# TouchController.net
KiCad netlist of a schematic drawn in Altium Designer
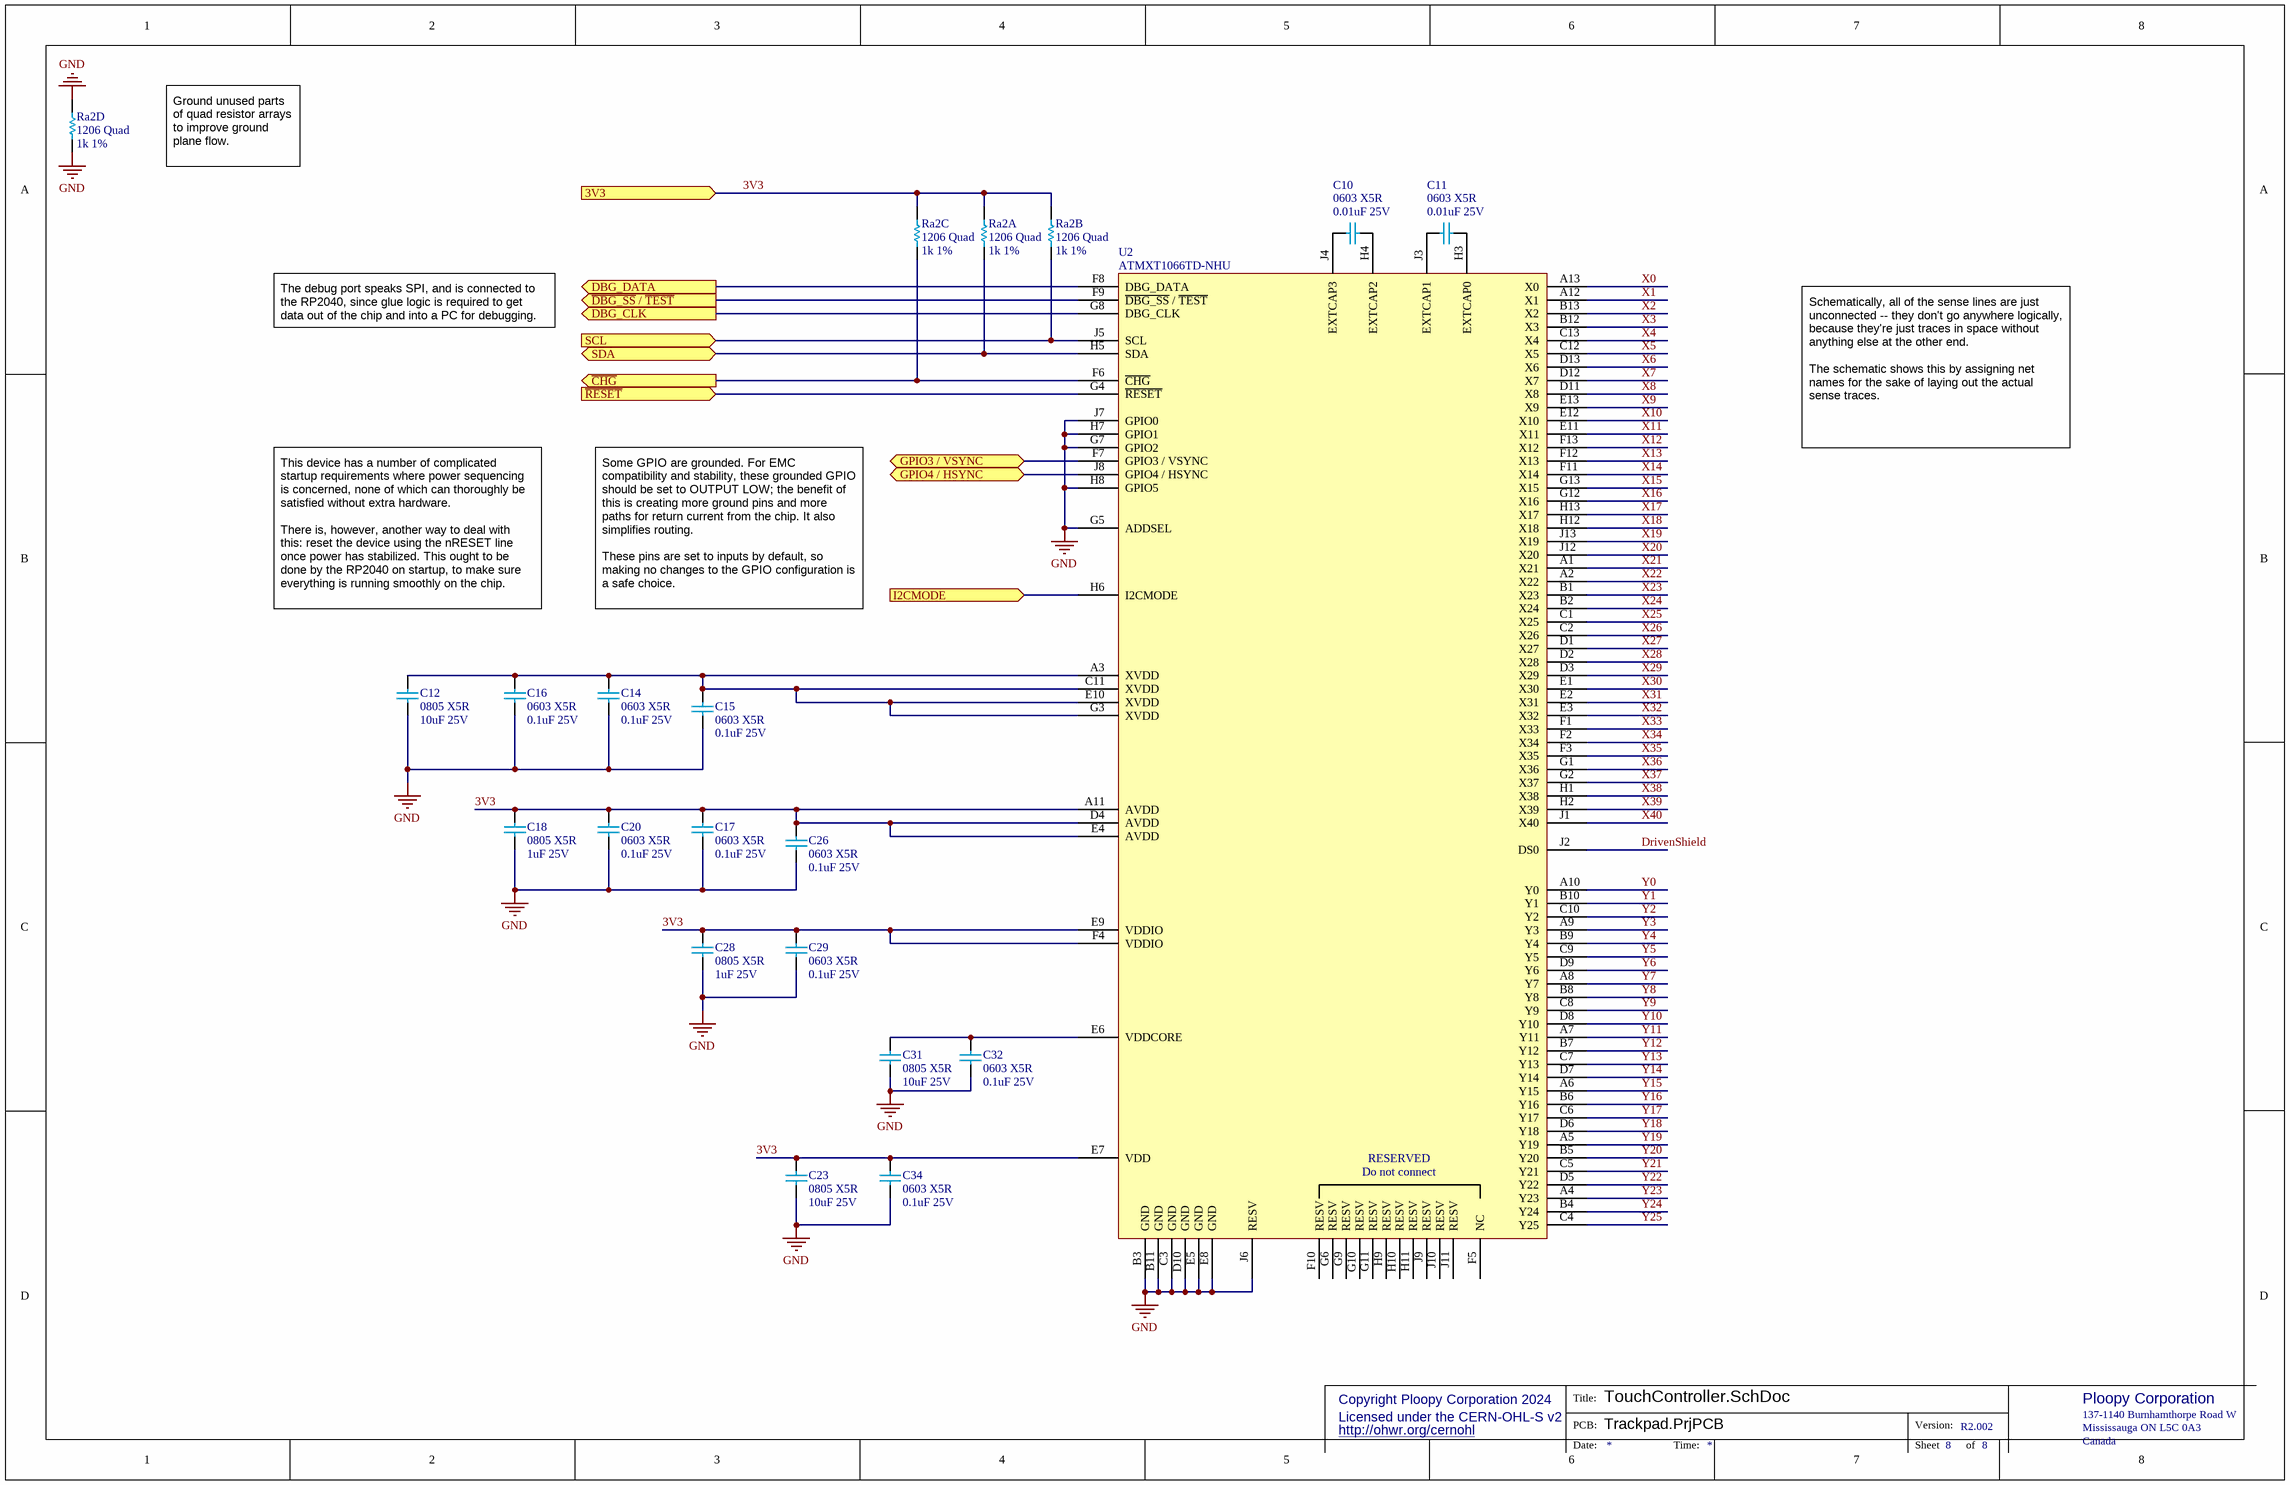
[diagram p0: TouchController.SchDoc]

(export (version "E")
  (design (tool "Eeschema 10.0.6"))
  (components
    (comp (ref "C10")
      (value "0603 X5R")
      (footprint "0603 capacitor - CAPC1608X06N")
      (description "0603, X5R or better")
      (fields (field (name "ALTIUM_VALUE") "0.01uF 25V"))
      (libsource (lib "Chip_Passives") (part "Cap 0.01uF 25V"))
    )
    (comp (ref "C11")
      (value "0603 X5R")
      (footprint "0603 capacitor - CAPC1608X06N")
      (description "0603, X5R or better")
      (fields (field (name "ALTIUM_VALUE") "0.01uF 25V"))
      (libsource (lib "Chip_Passives") (part "Cap 0.01uF 25V"))
    )
    (comp (ref "C12")
      (value "0805 X5R")
      (footprint "0805 - TALL")
      (description "0805, X5R or better")
      (fields (field (name "ALTIUM_VALUE") "10uF 25V"))
      (libsource (lib "Chip_Passives") (part "Cap 10uF 25V"))
    )
    (comp (ref "C14")
      (value "0603 X5R")
      (footprint "0603 capacitor - CAPC1608X06N")
      (description "0603, X5R or better")
      (fields (field (name "ALTIUM_VALUE") "0.1uF 25V"))
      (libsource (lib "Chip_Passives") (part "Cap 0.1uF 25V"))
    )
    (comp (ref "C15")
      (value "0603 X5R")
      (footprint "0603 capacitor - CAPC1608X06N")
      (description "0603, X5R or better")
      (fields (field (name "ALTIUM_VALUE") "0.1uF 25V"))
      (libsource (lib "Chip_Passives") (part "Cap 0.1uF 25V"))
    )
    (comp (ref "C16")
      (value "0603 X5R")
      (footprint "0603 capacitor - CAPC1608X06N")
      (description "0603, X5R or better")
      (fields (field (name "ALTIUM_VALUE") "0.1uF 25V"))
      (libsource (lib "Chip_Passives") (part "Cap 0.1uF 25V"))
    )
    (comp (ref "C17")
      (value "0603 X5R")
      (footprint "0603 capacitor - CAPC1608X06N")
      (description "0603, X5R or better")
      (fields (field (name "ALTIUM_VALUE") "0.1uF 25V"))
      (libsource (lib "Chip_Passives") (part "Cap 0.1uF 25V"))
    )
    (comp (ref "C18")
      (value "0805 X5R")
      (footprint "0805 - TALL")
      (description "0805, X5R or better")
      (fields (field (name "ALTIUM_VALUE") "1uF 25V"))
      (libsource (lib "Chip_Passives") (part "Cap 1uF 25V"))
    )
    (comp (ref "C20")
      (value "0603 X5R")
      (footprint "0603 capacitor - CAPC1608X06N")
      (description "0603, X5R or better")
      (fields (field (name "ALTIUM_VALUE") "0.1uF 25V"))
      (libsource (lib "Chip_Passives") (part "Cap 0.1uF 25V"))
    )
    (comp (ref "C23")
      (value "0805 X5R")
      (footprint "0805 - TALL")
      (description "0805, X5R or better")
      (fields (field (name "ALTIUM_VALUE") "10uF 25V"))
      (libsource (lib "Chip_Passives") (part "Cap 10uF 25V"))
    )
    (comp (ref "C26")
      (value "0603 X5R")
      (footprint "0603 capacitor - CAPC1608X06N")
      (description "0603, X5R or better")
      (fields (field (name "ALTIUM_VALUE") "0.1uF 25V"))
      (libsource (lib "Chip_Passives") (part "Cap 0.1uF 25V"))
    )
    (comp (ref "C28")
      (value "0805 X5R")
      (footprint "0805 - TALL")
      (description "0805, X5R or better")
      (fields (field (name "ALTIUM_VALUE") "1uF 25V"))
      (libsource (lib "Chip_Passives") (part "Cap 1uF 25V"))
    )
    (comp (ref "C29")
      (value "0603 X5R")
      (footprint "0603 capacitor - CAPC1608X06N")
      (description "0603, X5R or better")
      (fields (field (name "ALTIUM_VALUE") "0.1uF 25V"))
      (libsource (lib "Chip_Passives") (part "Cap 0.1uF 25V"))
    )
    (comp (ref "C31")
      (value "0805 X5R")
      (footprint "0805 - TALL")
      (description "0805, X5R or better")
      (fields (field (name "ALTIUM_VALUE") "10uF 25V"))
      (libsource (lib "Chip_Passives") (part "Cap 10uF 25V"))
    )
    (comp (ref "C32")
      (value "0603 X5R")
      (footprint "0603 capacitor - CAPC1608X06N")
      (description "0603, X5R or better")
      (fields (field (name "ALTIUM_VALUE") "0.1uF 25V"))
      (libsource (lib "Chip_Passives") (part "Cap 0.1uF 25V"))
    )
    (comp (ref "C34")
      (value "0603 X5R")
      (footprint "0603 capacitor - CAPC1608X06N")
      (description "0603, X5R or better")
      (fields (field (name "ALTIUM_VALUE") "0.1uF 25V"))
      (libsource (lib "Chip_Passives") (part "Cap 0.1uF 25V"))
    )
    (comp (ref "Ra2")
      (value "1206 Quad")
      (footprint "4x 1k 1% - CAC-80P320X160-8M")
      (description "Chip resistor")
      (fields (field (name "ALTIUM_VALUE") "1k 1%"))
      (libsource (lib "Chip_Passives") (part "Quad Res 1k 1% 1206"))
    )
    (comp (ref "U2")
      (value "ATMXT1066TD-NHU")
      (footprint "ATMXT1066TD-NHU - BGA117C65P13X9_950X700X65")
      (description "maXTouch 1066-node Touchscreen Controller")
      (libsource (lib "CapSense") (part "ATMXT1066TD-NHU"))
    )
  )
  (nets
    (net (code "1") (name "/3V3") (class "Default")
      (node (ref "C17") (pin "2") (pinfunction "2_2") (pintype "passive"))
      (node (ref "C18") (pin "2") (pinfunction "2_2") (pintype "passive"))
      (node (ref "C20") (pin "2") (pinfunction "2_2") (pintype "passive"))
      (node (ref "C23") (pin "2") (pinfunction "2_2") (pintype "passive"))
      (node (ref "C26") (pin "2") (pinfunction "2_2") (pintype "passive"))
      (node (ref "C28") (pin "2") (pinfunction "2_2") (pintype "passive"))
      (node (ref "C29") (pin "2") (pinfunction "2_2") (pintype "passive"))
      (node (ref "C34") (pin "2") (pinfunction "2_2") (pintype "passive"))
      (node (ref "Ra2") (pin "6") (pinfunction "6_6") (pintype "passive"))
      (node (ref "Ra2") (pin "7") (pinfunction "7_7") (pintype "passive"))
      (node (ref "Ra2") (pin "8") (pinfunction "8_8") (pintype "passive"))
      (node (ref "U2") (pin "A11") (pinfunction "AVDD_A11") (pintype "passive"))
      (node (ref "U2") (pin "D4") (pinfunction "AVDD_D4") (pintype "passive"))
      (node (ref "U2") (pin "E4") (pinfunction "AVDD_E4") (pintype "passive"))
      (node (ref "U2") (pin "E7") (pinfunction "VDD_E7") (pintype "passive"))
      (node (ref "U2") (pin "E9") (pinfunction "VDDIO_E9") (pintype "passive"))
      (node (ref "U2") (pin "F4") (pinfunction "VDDIO_F4") (pintype "passive"))
    )
    (net (code "2") (name "/DBG_CLK") (class "Default")
      (node (ref "U2") (pin "G8") (pinfunction "DBG_CLK_G8") (pintype "passive"))
    )
    (net (code "3") (name "/DBG_DATA") (class "Default")
      (node (ref "U2") (pin "F8") (pinfunction "DBG_DATA_F8") (pintype "passive"))
    )
    (net (code "4") (name "/DrivenShield") (class "Default")
      (node (ref "U2") (pin "J2") (pinfunction "DS0_J2") (pintype "passive"))
    )
    (net (code "5") (name "/GPIO3 {slash} VSYNC") (class "Default")
      (node (ref "U2") (pin "F7") (pinfunction "GPIO3_/_VSYNC_F7") (pintype "passive"))
    )
    (net (code "6") (name "/GPIO4 {slash} HSYNC") (class "Default")
      (node (ref "U2") (pin "J8") (pinfunction "GPIO4_/_HSYNC_J8") (pintype "passive"))
    )
    (net (code "7") (name "/I2CMODE") (class "Default")
      (node (ref "U2") (pin "H6") (pinfunction "I2CMODE_H6") (pintype "passive"))
    )
    (net (code "8") (name "/SCL") (class "Default")
      (node (ref "Ra2") (pin "2") (pinfunction "2_2") (pintype "passive"))
      (node (ref "U2") (pin "J5") (pinfunction "SCL_J5") (pintype "passive"))
    )
    (net (code "9") (name "/SDA") (class "Default")
      (node (ref "Ra2") (pin "1") (pinfunction "1_1") (pintype "passive"))
      (node (ref "U2") (pin "H5") (pinfunction "SDA_H5") (pintype "passive"))
    )
    (net (code "10") (name "/X0") (class "Default")
      (node (ref "U2") (pin "A13") (pinfunction "X0_A13") (pintype "passive"))
    )
    (net (code "11") (name "/X1") (class "Default")
      (node (ref "U2") (pin "A12") (pinfunction "X1_A12") (pintype "passive"))
    )
    (net (code "12") (name "/X2") (class "Default")
      (node (ref "U2") (pin "B13") (pinfunction "X2_B13") (pintype "passive"))
    )
    (net (code "13") (name "/X3") (class "Default")
      (node (ref "U2") (pin "B12") (pinfunction "X3_B12") (pintype "passive"))
    )
    (net (code "14") (name "/X4") (class "Default")
      (node (ref "U2") (pin "C13") (pinfunction "X4_C13") (pintype "passive"))
    )
    (net (code "15") (name "/X5") (class "Default")
      (node (ref "U2") (pin "C12") (pinfunction "X5_C12") (pintype "passive"))
    )
    (net (code "16") (name "/X6") (class "Default")
      (node (ref "U2") (pin "D13") (pinfunction "X6_D13") (pintype "passive"))
    )
    (net (code "17") (name "/X7") (class "Default")
      (node (ref "U2") (pin "D12") (pinfunction "X7_D12") (pintype "passive"))
    )
    (net (code "18") (name "/X8") (class "Default")
      (node (ref "U2") (pin "D11") (pinfunction "X8_D11") (pintype "passive"))
    )
    (net (code "19") (name "/X9") (class "Default")
      (node (ref "U2") (pin "E13") (pinfunction "X9_E13") (pintype "passive"))
    )
    (net (code "20") (name "/X10") (class "Default")
      (node (ref "U2") (pin "E12") (pinfunction "X10_E12") (pintype "passive"))
    )
    (net (code "21") (name "/X11") (class "Default")
      (node (ref "U2") (pin "E11") (pinfunction "X11_E11") (pintype "passive"))
    )
    (net (code "22") (name "/X12") (class "Default")
      (node (ref "U2") (pin "F13") (pinfunction "X12_F13") (pintype "passive"))
    )
    (net (code "23") (name "/X13") (class "Default")
      (node (ref "U2") (pin "F12") (pinfunction "X13_F12") (pintype "passive"))
    )
    (net (code "24") (name "/X14") (class "Default")
      (node (ref "U2") (pin "F11") (pinfunction "X14_F11") (pintype "passive"))
    )
    (net (code "25") (name "/X15") (class "Default")
      (node (ref "U2") (pin "G13") (pinfunction "X15_G13") (pintype "passive"))
    )
    (net (code "26") (name "/X16") (class "Default")
      (node (ref "U2") (pin "G12") (pinfunction "X16_G12") (pintype "passive"))
    )
    (net (code "27") (name "/X17") (class "Default")
      (node (ref "U2") (pin "H13") (pinfunction "X17_H13") (pintype "passive"))
    )
    (net (code "28") (name "/X18") (class "Default")
      (node (ref "U2") (pin "H12") (pinfunction "X18_H12") (pintype "passive"))
    )
    (net (code "29") (name "/X19") (class "Default")
      (node (ref "U2") (pin "J13") (pinfunction "X19_J13") (pintype "passive"))
    )
    (net (code "30") (name "/X20") (class "Default")
      (node (ref "U2") (pin "J12") (pinfunction "X20_J12") (pintype "passive"))
    )
    (net (code "31") (name "/X21") (class "Default")
      (node (ref "U2") (pin "A1") (pinfunction "X21_A1") (pintype "passive"))
    )
    (net (code "32") (name "/X22") (class "Default")
      (node (ref "U2") (pin "A2") (pinfunction "X22_A2") (pintype "passive"))
    )
    (net (code "33") (name "/X23") (class "Default")
      (node (ref "U2") (pin "B1") (pinfunction "X23_B1") (pintype "passive"))
    )
    (net (code "34") (name "/X24") (class "Default")
      (node (ref "U2") (pin "B2") (pinfunction "X24_B2") (pintype "passive"))
    )
    (net (code "35") (name "/X25") (class "Default")
      (node (ref "U2") (pin "C1") (pinfunction "X25_C1") (pintype "passive"))
    )
    (net (code "36") (name "/X26") (class "Default")
      (node (ref "U2") (pin "C2") (pinfunction "X26_C2") (pintype "passive"))
    )
    (net (code "37") (name "/X27") (class "Default")
      (node (ref "U2") (pin "D1") (pinfunction "X27_D1") (pintype "passive"))
    )
    (net (code "38") (name "/X28") (class "Default")
      (node (ref "U2") (pin "D2") (pinfunction "X28_D2") (pintype "passive"))
    )
    (net (code "39") (name "/X29") (class "Default")
      (node (ref "U2") (pin "D3") (pinfunction "X29_D3") (pintype "passive"))
    )
    (net (code "40") (name "/X30") (class "Default")
      (node (ref "U2") (pin "E1") (pinfunction "X30_E1") (pintype "passive"))
    )
    (net (code "41") (name "/X31") (class "Default")
      (node (ref "U2") (pin "E2") (pinfunction "X31_E2") (pintype "passive"))
    )
    (net (code "42") (name "/X32") (class "Default")
      (node (ref "U2") (pin "E3") (pinfunction "X32_E3") (pintype "passive"))
    )
    (net (code "43") (name "/X33") (class "Default")
      (node (ref "U2") (pin "F1") (pinfunction "X33_F1") (pintype "passive"))
    )
    (net (code "44") (name "/X34") (class "Default")
      (node (ref "U2") (pin "F2") (pinfunction "X34_F2") (pintype "passive"))
    )
    (net (code "45") (name "/X35") (class "Default")
      (node (ref "U2") (pin "F3") (pinfunction "X35_F3") (pintype "passive"))
    )
    (net (code "46") (name "/X36") (class "Default")
      (node (ref "U2") (pin "G1") (pinfunction "X36_G1") (pintype "passive"))
    )
    (net (code "47") (name "/X37") (class "Default")
      (node (ref "U2") (pin "G2") (pinfunction "X37_G2") (pintype "passive"))
    )
    (net (code "48") (name "/X38") (class "Default")
      (node (ref "U2") (pin "H1") (pinfunction "X38_H1") (pintype "passive"))
    )
    (net (code "49") (name "/X39") (class "Default")
      (node (ref "U2") (pin "H2") (pinfunction "X39_H2") (pintype "passive"))
    )
    (net (code "50") (name "/X40") (class "Default")
      (node (ref "U2") (pin "J1") (pinfunction "X40_J1") (pintype "passive"))
    )
    (net (code "51") (name "/Y0") (class "Default")
      (node (ref "U2") (pin "A10") (pinfunction "Y0_A10") (pintype "passive"))
    )
    (net (code "52") (name "/Y1") (class "Default")
      (node (ref "U2") (pin "B10") (pinfunction "Y1_B10") (pintype "passive"))
    )
    (net (code "53") (name "/Y2") (class "Default")
      (node (ref "U2") (pin "C10") (pinfunction "Y2_C10") (pintype "passive"))
    )
    (net (code "54") (name "/Y3") (class "Default")
      (node (ref "U2") (pin "A9") (pinfunction "Y3_A9") (pintype "passive"))
    )
    (net (code "55") (name "/Y4") (class "Default")
      (node (ref "U2") (pin "B9") (pinfunction "Y4_B9") (pintype "passive"))
    )
    (net (code "56") (name "/Y5") (class "Default")
      (node (ref "U2") (pin "C9") (pinfunction "Y5_C9") (pintype "passive"))
    )
    (net (code "57") (name "/Y6") (class "Default")
      (node (ref "U2") (pin "D9") (pinfunction "Y6_D9") (pintype "passive"))
    )
    (net (code "58") (name "/Y7") (class "Default")
      (node (ref "U2") (pin "A8") (pinfunction "Y7_A8") (pintype "passive"))
    )
    (net (code "59") (name "/Y8") (class "Default")
      (node (ref "U2") (pin "B8") (pinfunction "Y8_B8") (pintype "passive"))
    )
    (net (code "60") (name "/Y9") (class "Default")
      (node (ref "U2") (pin "C8") (pinfunction "Y9_C8") (pintype "passive"))
    )
    (net (code "61") (name "/Y10") (class "Default")
      (node (ref "U2") (pin "D8") (pinfunction "Y10_D8") (pintype "passive"))
    )
    (net (code "62") (name "/Y11") (class "Default")
      (node (ref "U2") (pin "A7") (pinfunction "Y11_A7") (pintype "passive"))
    )
    (net (code "63") (name "/Y12") (class "Default")
      (node (ref "U2") (pin "B7") (pinfunction "Y12_B7") (pintype "passive"))
    )
    (net (code "64") (name "/Y13") (class "Default")
      (node (ref "U2") (pin "C7") (pinfunction "Y13_C7") (pintype "passive"))
    )
    (net (code "65") (name "/Y14") (class "Default")
      (node (ref "U2") (pin "D7") (pinfunction "Y14_D7") (pintype "passive"))
    )
    (net (code "66") (name "/Y15") (class "Default")
      (node (ref "U2") (pin "A6") (pinfunction "Y15_A6") (pintype "passive"))
    )
    (net (code "67") (name "/Y16") (class "Default")
      (node (ref "U2") (pin "B6") (pinfunction "Y16_B6") (pintype "passive"))
    )
    (net (code "68") (name "/Y17") (class "Default")
      (node (ref "U2") (pin "C6") (pinfunction "Y17_C6") (pintype "passive"))
    )
    (net (code "69") (name "/Y18") (class "Default")
      (node (ref "U2") (pin "D6") (pinfunction "Y18_D6") (pintype "passive"))
    )
    (net (code "70") (name "/Y19") (class "Default")
      (node (ref "U2") (pin "A5") (pinfunction "Y19_A5") (pintype "passive"))
    )
    (net (code "71") (name "/Y20") (class "Default")
      (node (ref "U2") (pin "B5") (pinfunction "Y20_B5") (pintype "passive"))
    )
    (net (code "72") (name "/Y21") (class "Default")
      (node (ref "U2") (pin "C5") (pinfunction "Y21_C5") (pintype "passive"))
    )
    (net (code "73") (name "/Y22") (class "Default")
      (node (ref "U2") (pin "D5") (pinfunction "Y22_D5") (pintype "passive"))
    )
    (net (code "74") (name "/Y23") (class "Default")
      (node (ref "U2") (pin "A4") (pinfunction "Y23_A4") (pintype "passive"))
    )
    (net (code "75") (name "/Y24") (class "Default")
      (node (ref "U2") (pin "B4") (pinfunction "Y24_B4") (pintype "passive"))
    )
    (net (code "76") (name "/Y25") (class "Default")
      (node (ref "U2") (pin "C4") (pinfunction "Y25_C4") (pintype "passive"))
    )
    (net (code "77") (name "/~{CHG}") (class "Default")
      (node (ref "Ra2") (pin "3") (pinfunction "3_3") (pintype "passive"))
      (node (ref "U2") (pin "F6") (pinfunction "~{CHG}_F6") (pintype "passive"))
    )
    (net (code "78") (name "/~{DBG_SS} {slash} ~{TEST}") (class "Default")
      (node (ref "U2") (pin "F9") (pinfunction "~{DBG_SS}_/_~{TEST}_F9") (pintype "passive"))
    )
    (net (code "79") (name "/~{RESET}") (class "Default")
      (node (ref "U2") (pin "G4") (pinfunction "~{RESET}_G4") (pintype "passive"))
    )
    (net (code "80") (name "GND") (class "Default")
      (node (ref "C12") (pin "1") (pinfunction "1_1") (pintype "passive"))
      (node (ref "C14") (pin "1") (pinfunction "1_1") (pintype "passive"))
      (node (ref "C15") (pin "1") (pinfunction "1_1") (pintype "passive"))
      (node (ref "C16") (pin "1") (pinfunction "1_1") (pintype "passive"))
      (node (ref "C17") (pin "1") (pinfunction "1_1") (pintype "passive"))
      (node (ref "C18") (pin "1") (pinfunction "1_1") (pintype "passive"))
      (node (ref "C20") (pin "1") (pinfunction "1_1") (pintype "passive"))
      (node (ref "C23") (pin "1") (pinfunction "1_1") (pintype "passive"))
      (node (ref "C26") (pin "1") (pinfunction "1_1") (pintype "passive"))
      (node (ref "C28") (pin "1") (pinfunction "1_1") (pintype "passive"))
      (node (ref "C29") (pin "1") (pinfunction "1_1") (pintype "passive"))
      (node (ref "C31") (pin "1") (pinfunction "1_1") (pintype "passive"))
      (node (ref "C32") (pin "1") (pinfunction "1_1") (pintype "passive"))
      (node (ref "C34") (pin "1") (pinfunction "1_1") (pintype "passive"))
      (node (ref "Ra2") (pin "4") (pinfunction "4_4") (pintype "passive"))
      (node (ref "Ra2") (pin "5") (pinfunction "5_5") (pintype "passive"))
      (node (ref "U2") (pin "B11") (pinfunction "GND_B11") (pintype "passive"))
      (node (ref "U2") (pin "B3") (pinfunction "GND_B3") (pintype "passive"))
      (node (ref "U2") (pin "C3") (pinfunction "GND_C3") (pintype "passive"))
      (node (ref "U2") (pin "D10") (pinfunction "GND_D10") (pintype "passive"))
      (node (ref "U2") (pin "E5") (pinfunction "GND_E5") (pintype "passive"))
      (node (ref "U2") (pin "E8") (pinfunction "GND_E8") (pintype "passive"))
      (node (ref "U2") (pin "G5") (pinfunction "ADDSEL_G5") (pintype "passive"))
      (node (ref "U2") (pin "G7") (pinfunction "GPIO2_G7") (pintype "passive"))
      (node (ref "U2") (pin "H7") (pinfunction "GPIO1_H7") (pintype "passive"))
      (node (ref "U2") (pin "H8") (pinfunction "GPIO5_H8") (pintype "passive"))
      (node (ref "U2") (pin "J6") (pinfunction "RESV_J6") (pintype "passive"))
      (node (ref "U2") (pin "J7") (pinfunction "GPIO0_J7") (pintype "passive"))
    )
    (net (code "81") (name "Net-(C12-Pad2)") (class "Default")
      (node (ref "C12") (pin "2") (pinfunction "2_2") (pintype "passive"))
      (node (ref "C14") (pin "2") (pinfunction "2_2") (pintype "passive"))
      (node (ref "C15") (pin "2") (pinfunction "2_2") (pintype "passive"))
      (node (ref "C16") (pin "2") (pinfunction "2_2") (pintype "passive"))
      (node (ref "U2") (pin "A3") (pinfunction "XVDD_A3") (pintype "passive"))
      (node (ref "U2") (pin "C11") (pinfunction "XVDD_C11") (pintype "passive"))
      (node (ref "U2") (pin "E10") (pinfunction "XVDD_E10") (pintype "passive"))
      (node (ref "U2") (pin "G3") (pinfunction "XVDD_G3") (pintype "passive"))
    )
    (net (code "82") (name "Net-(U2-EXTCAP0)") (class "Default")
      (node (ref "C11") (pin "1") (pinfunction "1_1") (pintype "passive"))
      (node (ref "U2") (pin "H3") (pinfunction "EXTCAP0_H3") (pintype "passive"))
    )
    (net (code "83") (name "Net-(U2-EXTCAP1)") (class "Default")
      (node (ref "C11") (pin "2") (pinfunction "2_2") (pintype "passive"))
      (node (ref "U2") (pin "J3") (pinfunction "EXTCAP1_J3") (pintype "passive"))
    )
    (net (code "84") (name "Net-(U2-EXTCAP2)") (class "Default")
      (node (ref "C10") (pin "2") (pinfunction "2_2") (pintype "passive"))
      (node (ref "U2") (pin "H4") (pinfunction "EXTCAP2_H4") (pintype "passive"))
    )
    (net (code "85") (name "Net-(U2-EXTCAP3)") (class "Default")
      (node (ref "C10") (pin "1") (pinfunction "1_1") (pintype "passive"))
      (node (ref "U2") (pin "J4") (pinfunction "EXTCAP3_J4") (pintype "passive"))
    )
    (net (code "86") (name "Net-(U2-VDDCORE)") (class "Default")
      (node (ref "C31") (pin "2") (pinfunction "2_2") (pintype "passive"))
      (node (ref "C32") (pin "2") (pinfunction "2_2") (pintype "passive"))
      (node (ref "U2") (pin "E6") (pinfunction "VDDCORE_E6") (pintype "passive"))
    )
    (net (code "87") (name "unconnected-(U2-NC-PadF5)") (class "Default")
      (node (ref "U2") (pin "F5") (pinfunction "NC_F5") (pintype "passive"))
    )
    (net (code "88") (name "unconnected-(U2-RESV-PadF10)") (class "Default")
      (node (ref "U2") (pin "F10") (pinfunction "RESV_F10") (pintype "passive"))
    )
    (net (code "89") (name "unconnected-(U2-RESV-PadG6)") (class "Default")
      (node (ref "U2") (pin "G6") (pinfunction "RESV_G6") (pintype "passive"))
    )
    (net (code "90") (name "unconnected-(U2-RESV-PadG9)") (class "Default")
      (node (ref "U2") (pin "G9") (pinfunction "RESV_G9") (pintype "passive"))
    )
    (net (code "91") (name "unconnected-(U2-RESV-PadG10)") (class "Default")
      (node (ref "U2") (pin "G10") (pinfunction "RESV_G10") (pintype "passive"))
    )
    (net (code "92") (name "unconnected-(U2-RESV-PadG11)") (class "Default")
      (node (ref "U2") (pin "G11") (pinfunction "RESV_G11") (pintype "passive"))
    )
    (net (code "93") (name "unconnected-(U2-RESV-PadH9)") (class "Default")
      (node (ref "U2") (pin "H9") (pinfunction "RESV_H9") (pintype "passive"))
    )
    (net (code "94") (name "unconnected-(U2-RESV-PadH10)") (class "Default")
      (node (ref "U2") (pin "H10") (pinfunction "RESV_H10") (pintype "passive"))
    )
    (net (code "95") (name "unconnected-(U2-RESV-PadH11)") (class "Default")
      (node (ref "U2") (pin "H11") (pinfunction "RESV_H11") (pintype "passive"))
    )
    (net (code "96") (name "unconnected-(U2-RESV-PadJ9)") (class "Default")
      (node (ref "U2") (pin "J9") (pinfunction "RESV_J9") (pintype "passive"))
    )
    (net (code "97") (name "unconnected-(U2-RESV-PadJ10)") (class "Default")
      (node (ref "U2") (pin "J10") (pinfunction "RESV_J10") (pintype "passive"))
    )
    (net (code "98") (name "unconnected-(U2-RESV-PadJ11)") (class "Default")
      (node (ref "U2") (pin "J11") (pinfunction "RESV_J11") (pintype "passive"))
    )
  )
)
